# LTC1473.net
KiCad netlist of a schematic drawn in Altium Designer
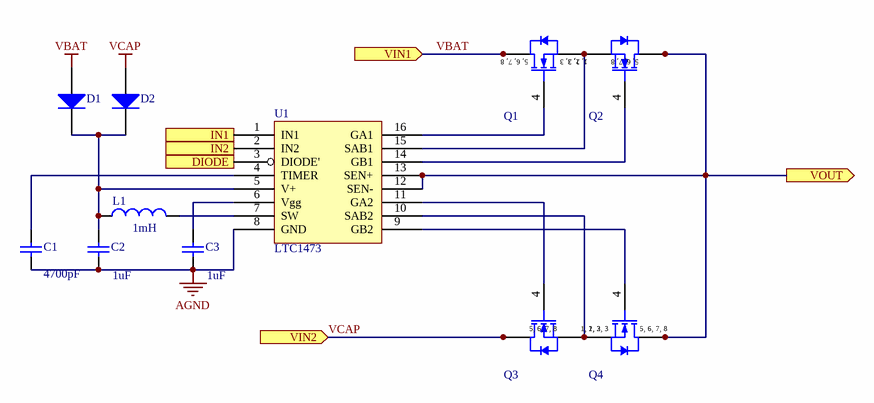
[diagram p0: LTC1473.SchDoc]

(export (version "E")
  (design (tool "Eeschema 10.0.6"))
  (components
    (comp (ref "C1")
      (value "4700pF")
      (footprint "C 0603_L")
      (description "X5R 50V")
      (fields (field (name "Comment") "Cap") (field (name "PUBLISHER") "Altium Limited"))
      (libsource (lib "Miscellaneous Devices") (part "Cap"))
    )
    (comp (ref "C2")
      (value "1uF")
      (footprint "C 0603_L")
      (description "X5R 50V")
      (fields (field (name "Comment") "Cap") (field (name "PUBLISHER") "Altium Limited"))
      (libsource (lib "Miscellaneous Devices") (part "Cap"))
    )
    (comp (ref "C3")
      (value "1uF")
      (footprint "C 0603_L")
      (description "X5R 50V")
      (fields (field (name "Comment") "Cap") (field (name "PUBLISHER") "Altium Limited"))
      (libsource (lib "Miscellaneous Devices") (part "Cap"))
    )
    (comp (ref "D1")
      (value "Diode")
      (footprint "SOD-523")
      (description "SS14")
      (fields (field (name "PUBLISHER") "Altium Limited"))
      (libsource (lib "Miscellaneous Devices") (part "Diode"))
    )
    (comp (ref "D2")
      (value "Diode")
      (footprint "SOD-523")
      (description "SS14")
      (fields (field (name "PUBLISHER") "Altium Limited"))
      (libsource (lib "Miscellaneous Devices") (part "Diode"))
    )
    (comp (ref "L1")
      (value "1mH")
      (footprint "1812LS-105XKBC")
      (description "1812LS-105XKBC")
      (fields (field (name "Comment") "Inductor") (field (name "PUBLISHER") "Altium Limited"))
      (libsource (lib "Miscellaneous Devices") (part "Inductor"))
    )
    (comp (ref "Q1")
      (value "BSC028N06NS G")
      (footprint "INF-PG-TDSON-8-1_V")
      (fields (field (name "MANUFACTURER") "Infineon") (field (name "PARTNUMBER") "BSC118N10NS G"))
      (libsource (lib "Infineon_Power_MOSFET") (part "BSC118N10NS G"))
    )
    (comp (ref "Q2")
      (value "BSC028N06NS G")
      (footprint "INF-PG-TDSON-8-1_V")
      (fields (field (name "MANUFACTURER") "Infineon") (field (name "PARTNUMBER") "BSC118N10NS G"))
      (libsource (lib "Infineon_Power_MOSFET") (part "BSC118N10NS G"))
    )
    (comp (ref "Q3")
      (value "BSC028N06NS G")
      (footprint "INF-PG-TDSON-8-1_V")
      (fields (field (name "MANUFACTURER") "Infineon") (field (name "PARTNUMBER") "BSC118N10NS G"))
      (libsource (lib "Infineon_Power_MOSFET") (part "BSC118N10NS G"))
    )
    (comp (ref "Q4")
      (value "BSC028N06NS G")
      (footprint "INF-PG-TDSON-8-1_V")
      (fields (field (name "MANUFACTURER") "Infineon") (field (name "PARTNUMBER") "BSC118N10NS G"))
      (libsource (lib "Infineon_Power_MOSFET") (part "BSC118N10NS G"))
    )
    (comp (ref "U1") (value "LTC1473") (footprint "SSOP16_N") (libsource (lib "ADI芯片") (part "LTC1473")))
  )
  (nets
    (net (code "1") (name "/DIODE") (class "Default")
      (node (ref "U1") (pin "3") (pinfunction "DIODE'_3") (pintype "passive"))
    )
    (net (code "2") (name "/IN1") (class "Default")
      (node (ref "U1") (pin "1") (pinfunction "IN1_1") (pintype "passive"))
    )
    (net (code "3") (name "/IN2") (class "Default")
      (node (ref "U1") (pin "2") (pinfunction "IN2_2") (pintype "passive"))
    )
    (net (code "4") (name "/VOUT") (class "Default")
      (node (ref "Q2") (pin "5") (pinfunction "DRAIN_5") (pintype "passive"))
      (node (ref "Q2") (pin "6") (pinfunction "DRAIN_6") (pintype "passive"))
      (node (ref "Q2") (pin "7") (pinfunction "DRAIN_7") (pintype "passive"))
      (node (ref "Q2") (pin "8") (pinfunction "DRAIN_8") (pintype "passive"))
      (node (ref "Q4") (pin "5") (pinfunction "DRAIN_5") (pintype "passive"))
      (node (ref "Q4") (pin "6") (pinfunction "DRAIN_6") (pintype "passive"))
      (node (ref "Q4") (pin "7") (pinfunction "DRAIN_7") (pintype "passive"))
      (node (ref "Q4") (pin "8") (pinfunction "DRAIN_8") (pintype "passive"))
      (node (ref "U1") (pin "12") (pinfunction "SEN-_12") (pintype "passive"))
      (node (ref "U1") (pin "13") (pinfunction "SEN+_13") (pintype "passive"))
    )
    (net (code "5") (name "AGND") (class "Default")
      (node (ref "C1") (pin "1") (pinfunction "1_1") (pintype "passive"))
      (node (ref "C2") (pin "1") (pinfunction "1_1") (pintype "passive"))
      (node (ref "C3") (pin "1") (pinfunction "1_1") (pintype "passive"))
      (node (ref "U1") (pin "8") (pinfunction "GND_8") (pintype "passive"))
    )
    (net (code "6") (name "Net-(D1-K)") (class "Default")
      (node (ref "C2") (pin "2") (pinfunction "2_2") (pintype "passive"))
      (node (ref "D1") (pin "2") (pinfunction "K_2") (pintype "passive"))
      (node (ref "D2") (pin "2") (pinfunction "K_2") (pintype "passive"))
      (node (ref "L1") (pin "1") (pinfunction "1_1") (pintype "passive"))
      (node (ref "U1") (pin "5") (pinfunction "V+_5") (pintype "passive"))
    )
    (net (code "7") (name "Net-(Q1-GATE)") (class "Default")
      (node (ref "Q1") (pin "4") (pinfunction "GATE_4") (pintype "passive"))
      (node (ref "U1") (pin "16") (pinfunction "GA1_16") (pintype "passive"))
    )
    (net (code "8") (name "Net-(Q2-GATE)") (class "Default")
      (node (ref "Q2") (pin "4") (pinfunction "GATE_4") (pintype "passive"))
      (node (ref "U1") (pin "14") (pinfunction "GB1_14") (pintype "passive"))
    )
    (net (code "9") (name "Net-(Q3-GATE)") (class "Default")
      (node (ref "Q3") (pin "4") (pinfunction "GATE_4") (pintype "passive"))
      (node (ref "U1") (pin "11") (pinfunction "GA2_11") (pintype "passive"))
    )
    (net (code "10") (name "Net-(Q4-GATE)") (class "Default")
      (node (ref "Q4") (pin "4") (pinfunction "GATE_4") (pintype "passive"))
      (node (ref "U1") (pin "9") (pinfunction "GB2_9") (pintype "passive"))
    )
    (net (code "11") (name "Net-(U1-SAB1)") (class "Default")
      (node (ref "Q1") (pin "1") (pinfunction "SOURCE_1") (pintype "passive"))
      (node (ref "Q1") (pin "2") (pinfunction "SOURCE_2") (pintype "passive"))
      (node (ref "Q1") (pin "3") (pinfunction "SOURCE_3") (pintype "passive"))
      (node (ref "Q2") (pin "1") (pinfunction "SOURCE_1") (pintype "passive"))
      (node (ref "Q2") (pin "2") (pinfunction "SOURCE_2") (pintype "passive"))
      (node (ref "Q2") (pin "3") (pinfunction "SOURCE_3") (pintype "passive"))
      (node (ref "U1") (pin "15") (pinfunction "SAB1_15") (pintype "passive"))
    )
    (net (code "12") (name "Net-(U1-SAB2)") (class "Default")
      (node (ref "Q3") (pin "1") (pinfunction "SOURCE_1") (pintype "passive"))
      (node (ref "Q3") (pin "2") (pinfunction "SOURCE_2") (pintype "passive"))
      (node (ref "Q3") (pin "3") (pinfunction "SOURCE_3") (pintype "passive"))
      (node (ref "Q4") (pin "1") (pinfunction "SOURCE_1") (pintype "passive"))
      (node (ref "Q4") (pin "2") (pinfunction "SOURCE_2") (pintype "passive"))
      (node (ref "Q4") (pin "3") (pinfunction "SOURCE_3") (pintype "passive"))
      (node (ref "U1") (pin "10") (pinfunction "SAB2_10") (pintype "passive"))
    )
    (net (code "13") (name "Net-(U1-SW)") (class "Default")
      (node (ref "L1") (pin "2") (pinfunction "2_2") (pintype "passive"))
      (node (ref "U1") (pin "7") (pinfunction "SW_7") (pintype "passive"))
    )
    (net (code "14") (name "Net-(U1-TIMER)") (class "Default")
      (node (ref "C1") (pin "2") (pinfunction "2_2") (pintype "passive"))
      (node (ref "U1") (pin "4") (pinfunction "TIMER_4") (pintype "passive"))
    )
    (net (code "15") (name "Net-(U1-Vgg)") (class "Default")
      (node (ref "C3") (pin "2") (pinfunction "2_2") (pintype "passive"))
      (node (ref "U1") (pin "6") (pinfunction "Vgg_6") (pintype "passive"))
    )
    (net (code "16") (name "VBAT") (class "Default")
      (node (ref "D1") (pin "1") (pinfunction "A_1") (pintype "passive"))
      (node (ref "Q1") (pin "5") (pinfunction "DRAIN_5") (pintype "passive"))
      (node (ref "Q1") (pin "6") (pinfunction "DRAIN_6") (pintype "passive"))
      (node (ref "Q1") (pin "7") (pinfunction "DRAIN_7") (pintype "passive"))
      (node (ref "Q1") (pin "8") (pinfunction "DRAIN_8") (pintype "passive"))
    )
    (net (code "17") (name "VCAP") (class "Default")
      (node (ref "D2") (pin "1") (pinfunction "A_1") (pintype "passive"))
      (node (ref "Q3") (pin "5") (pinfunction "DRAIN_5") (pintype "passive"))
      (node (ref "Q3") (pin "6") (pinfunction "DRAIN_6") (pintype "passive"))
      (node (ref "Q3") (pin "7") (pinfunction "DRAIN_7") (pintype "passive"))
      (node (ref "Q3") (pin "8") (pinfunction "DRAIN_8") (pintype "passive"))
    )
  )
)
